# Tesla_MMC.net
KiCad netlist of a schematic drawn in Altium Designer
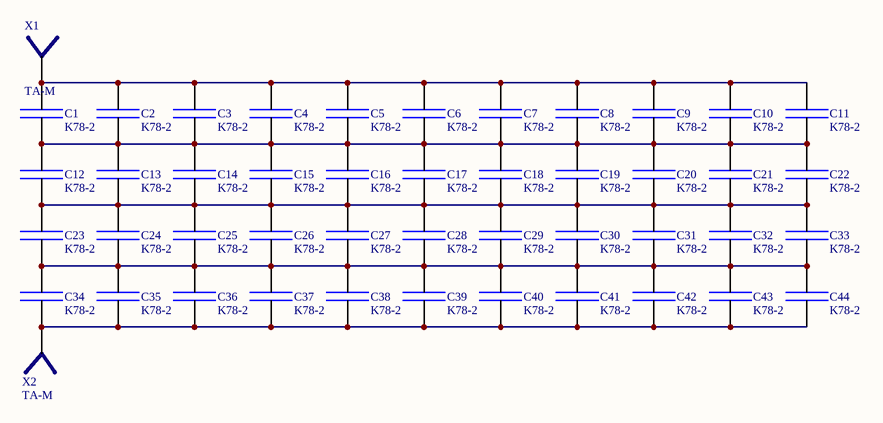
[diagram p0: Tesla_MMC.SchDoc]

(export (version "E")
  (design (tool "Eeschema 10.0.6"))
  (components
    (comp (ref "C1")
      (value "K78-2")
      (footprint "Capasitor K78-2")
      (libsource (lib "NEW") (part "Capasitor_K78-2"))
    )
    (comp (ref "C2")
      (value "K78-2")
      (footprint "Capasitor K78-2")
      (libsource (lib "NEW") (part "Capasitor_K78-2"))
    )
    (comp (ref "C3")
      (value "K78-2")
      (footprint "Capasitor K78-2")
      (libsource (lib "NEW") (part "Capasitor_K78-2"))
    )
    (comp (ref "C4")
      (value "K78-2")
      (footprint "Capasitor K78-2")
      (libsource (lib "NEW") (part "Capasitor_K78-2"))
    )
    (comp (ref "C5")
      (value "K78-2")
      (footprint "Capasitor K78-2")
      (libsource (lib "NEW") (part "Capasitor_K78-2"))
    )
    (comp (ref "C6")
      (value "K78-2")
      (footprint "Capasitor K78-2")
      (libsource (lib "NEW") (part "Capasitor_K78-2"))
    )
    (comp (ref "C7")
      (value "K78-2")
      (footprint "Capasitor K78-2")
      (libsource (lib "NEW") (part "Capasitor_K78-2"))
    )
    (comp (ref "C8")
      (value "K78-2")
      (footprint "Capasitor K78-2")
      (libsource (lib "NEW") (part "Capasitor_K78-2"))
    )
    (comp (ref "C9")
      (value "K78-2")
      (footprint "Capasitor K78-2")
      (libsource (lib "NEW") (part "Capasitor_K78-2"))
    )
    (comp (ref "C10")
      (value "K78-2")
      (footprint "Capasitor K78-2")
      (libsource (lib "NEW") (part "Capasitor_K78-2"))
    )
    (comp (ref "C11")
      (value "K78-2")
      (footprint "Capasitor K78-2")
      (libsource (lib "NEW") (part "Capasitor_K78-2"))
    )
    (comp (ref "C12")
      (value "K78-2")
      (footprint "Capasitor K78-2")
      (libsource (lib "NEW") (part "Capasitor_K78-2"))
    )
    (comp (ref "C13")
      (value "K78-2")
      (footprint "Capasitor K78-2")
      (libsource (lib "NEW") (part "Capasitor_K78-2"))
    )
    (comp (ref "C14")
      (value "K78-2")
      (footprint "Capasitor K78-2")
      (libsource (lib "NEW") (part "Capasitor_K78-2"))
    )
    (comp (ref "C15")
      (value "K78-2")
      (footprint "Capasitor K78-2")
      (libsource (lib "NEW") (part "Capasitor_K78-2"))
    )
    (comp (ref "C16")
      (value "K78-2")
      (footprint "Capasitor K78-2")
      (libsource (lib "NEW") (part "Capasitor_K78-2"))
    )
    (comp (ref "C17")
      (value "K78-2")
      (footprint "Capasitor K78-2")
      (libsource (lib "NEW") (part "Capasitor_K78-2"))
    )
    (comp (ref "C18")
      (value "K78-2")
      (footprint "Capasitor K78-2")
      (libsource (lib "NEW") (part "Capasitor_K78-2"))
    )
    (comp (ref "C19")
      (value "K78-2")
      (footprint "Capasitor K78-2")
      (libsource (lib "NEW") (part "Capasitor_K78-2"))
    )
    (comp (ref "C20")
      (value "K78-2")
      (footprint "Capasitor K78-2")
      (libsource (lib "NEW") (part "Capasitor_K78-2"))
    )
    (comp (ref "C21")
      (value "K78-2")
      (footprint "Capasitor K78-2")
      (libsource (lib "NEW") (part "Capasitor_K78-2"))
    )
    (comp (ref "C22")
      (value "K78-2")
      (footprint "Capasitor K78-2")
      (libsource (lib "NEW") (part "Capasitor_K78-2"))
    )
    (comp (ref "C23")
      (value "K78-2")
      (footprint "Capasitor K78-2")
      (libsource (lib "NEW") (part "Capasitor_K78-2"))
    )
    (comp (ref "C24")
      (value "K78-2")
      (footprint "Capasitor K78-2")
      (libsource (lib "NEW") (part "Capasitor_K78-2"))
    )
    (comp (ref "C25")
      (value "K78-2")
      (footprint "Capasitor K78-2")
      (libsource (lib "NEW") (part "Capasitor_K78-2"))
    )
    (comp (ref "C26")
      (value "K78-2")
      (footprint "Capasitor K78-2")
      (libsource (lib "NEW") (part "Capasitor_K78-2"))
    )
    (comp (ref "C27")
      (value "K78-2")
      (footprint "Capasitor K78-2")
      (libsource (lib "NEW") (part "Capasitor_K78-2"))
    )
    (comp (ref "C28")
      (value "K78-2")
      (footprint "Capasitor K78-2")
      (libsource (lib "NEW") (part "Capasitor_K78-2"))
    )
    (comp (ref "C29")
      (value "K78-2")
      (footprint "Capasitor K78-2")
      (libsource (lib "NEW") (part "Capasitor_K78-2"))
    )
    (comp (ref "C30")
      (value "K78-2")
      (footprint "Capasitor K78-2")
      (libsource (lib "NEW") (part "Capasitor_K78-2"))
    )
    (comp (ref "C31")
      (value "K78-2")
      (footprint "Capasitor K78-2")
      (libsource (lib "NEW") (part "Capasitor_K78-2"))
    )
    (comp (ref "C32")
      (value "K78-2")
      (footprint "Capasitor K78-2")
      (libsource (lib "NEW") (part "Capasitor_K78-2"))
    )
    (comp (ref "C33")
      (value "K78-2")
      (footprint "Capasitor K78-2")
      (libsource (lib "NEW") (part "Capasitor_K78-2"))
    )
    (comp (ref "C34")
      (value "K78-2")
      (footprint "Capasitor K78-2")
      (libsource (lib "NEW") (part "Capasitor_K78-2"))
    )
    (comp (ref "C35")
      (value "K78-2")
      (footprint "Capasitor K78-2")
      (libsource (lib "NEW") (part "Capasitor_K78-2"))
    )
    (comp (ref "C36")
      (value "K78-2")
      (footprint "Capasitor K78-2")
      (libsource (lib "NEW") (part "Capasitor_K78-2"))
    )
    (comp (ref "C37")
      (value "K78-2")
      (footprint "Capasitor K78-2")
      (libsource (lib "NEW") (part "Capasitor_K78-2"))
    )
    (comp (ref "C38")
      (value "K78-2")
      (footprint "Capasitor K78-2")
      (libsource (lib "NEW") (part "Capasitor_K78-2"))
    )
    (comp (ref "C39")
      (value "K78-2")
      (footprint "Capasitor K78-2")
      (libsource (lib "NEW") (part "Capasitor_K78-2"))
    )
    (comp (ref "C40")
      (value "K78-2")
      (footprint "Capasitor K78-2")
      (libsource (lib "NEW") (part "Capasitor_K78-2"))
    )
    (comp (ref "C41")
      (value "K78-2")
      (footprint "Capasitor K78-2")
      (libsource (lib "NEW") (part "Capasitor_K78-2"))
    )
    (comp (ref "C42")
      (value "K78-2")
      (footprint "Capasitor K78-2")
      (libsource (lib "NEW") (part "Capasitor_K78-2"))
    )
    (comp (ref "C43")
      (value "K78-2")
      (footprint "Capasitor K78-2")
      (libsource (lib "NEW") (part "Capasitor_K78-2"))
    )
    (comp (ref "C44")
      (value "K78-2")
      (footprint "Capasitor K78-2")
      (libsource (lib "NEW") (part "Capasitor_K78-2"))
    )
    (comp (ref "X1") (value "TA-M") (footprint "TA-M") (libsource (lib "NEW") (part "TA-M")))
    (comp (ref "X2") (value "TA-M") (footprint "TA-M") (libsource (lib "NEW") (part "TA-M")))
  )
  (nets
    (net (code "1") (name "Net-(C1-Pad1)") (class "Default")
      (node (ref "C1") (pin "1") (pintype "passive"))
      (node (ref "C10") (pin "1") (pintype "passive"))
      (node (ref "C11") (pin "1") (pintype "passive"))
      (node (ref "C2") (pin "1") (pintype "passive"))
      (node (ref "C3") (pin "1") (pintype "passive"))
      (node (ref "C4") (pin "1") (pintype "passive"))
      (node (ref "C5") (pin "1") (pintype "passive"))
      (node (ref "C6") (pin "1") (pintype "passive"))
      (node (ref "C7") (pin "1") (pintype "passive"))
      (node (ref "C8") (pin "1") (pintype "passive"))
      (node (ref "C9") (pin "1") (pintype "passive"))
      (node (ref "X1") (pin "1") (pintype "passive"))
    )
    (net (code "2") (name "Net-(C1-Pad2)") (class "Default")
      (node (ref "C1") (pin "2") (pintype "passive"))
      (node (ref "C10") (pin "2") (pintype "passive"))
      (node (ref "C11") (pin "2") (pintype "passive"))
      (node (ref "C12") (pin "1") (pintype "passive"))
      (node (ref "C13") (pin "1") (pintype "passive"))
      (node (ref "C14") (pin "1") (pintype "passive"))
      (node (ref "C15") (pin "1") (pintype "passive"))
      (node (ref "C16") (pin "1") (pintype "passive"))
      (node (ref "C17") (pin "1") (pintype "passive"))
      (node (ref "C18") (pin "1") (pintype "passive"))
      (node (ref "C19") (pin "1") (pintype "passive"))
      (node (ref "C2") (pin "2") (pintype "passive"))
      (node (ref "C20") (pin "1") (pintype "passive"))
      (node (ref "C21") (pin "1") (pintype "passive"))
      (node (ref "C22") (pin "1") (pintype "passive"))
      (node (ref "C3") (pin "2") (pintype "passive"))
      (node (ref "C4") (pin "2") (pintype "passive"))
      (node (ref "C5") (pin "2") (pintype "passive"))
      (node (ref "C6") (pin "2") (pintype "passive"))
      (node (ref "C7") (pin "2") (pintype "passive"))
      (node (ref "C8") (pin "2") (pintype "passive"))
      (node (ref "C9") (pin "2") (pintype "passive"))
    )
    (net (code "3") (name "Net-(C12-Pad2)") (class "Default")
      (node (ref "C12") (pin "2") (pintype "passive"))
      (node (ref "C13") (pin "2") (pintype "passive"))
      (node (ref "C14") (pin "2") (pintype "passive"))
      (node (ref "C15") (pin "2") (pintype "passive"))
      (node (ref "C16") (pin "2") (pintype "passive"))
      (node (ref "C17") (pin "2") (pintype "passive"))
      (node (ref "C18") (pin "2") (pintype "passive"))
      (node (ref "C19") (pin "2") (pintype "passive"))
      (node (ref "C20") (pin "2") (pintype "passive"))
      (node (ref "C21") (pin "2") (pintype "passive"))
      (node (ref "C22") (pin "2") (pintype "passive"))
      (node (ref "C23") (pin "1") (pintype "passive"))
      (node (ref "C24") (pin "1") (pintype "passive"))
      (node (ref "C25") (pin "1") (pintype "passive"))
      (node (ref "C26") (pin "1") (pintype "passive"))
      (node (ref "C27") (pin "1") (pintype "passive"))
      (node (ref "C28") (pin "1") (pintype "passive"))
      (node (ref "C29") (pin "1") (pintype "passive"))
      (node (ref "C30") (pin "1") (pintype "passive"))
      (node (ref "C31") (pin "1") (pintype "passive"))
      (node (ref "C32") (pin "1") (pintype "passive"))
      (node (ref "C33") (pin "1") (pintype "passive"))
    )
    (net (code "4") (name "Net-(C23-Pad2)") (class "Default")
      (node (ref "C23") (pin "2") (pintype "passive"))
      (node (ref "C24") (pin "2") (pintype "passive"))
      (node (ref "C25") (pin "2") (pintype "passive"))
      (node (ref "C26") (pin "2") (pintype "passive"))
      (node (ref "C27") (pin "2") (pintype "passive"))
      (node (ref "C28") (pin "2") (pintype "passive"))
      (node (ref "C29") (pin "2") (pintype "passive"))
      (node (ref "C30") (pin "2") (pintype "passive"))
      (node (ref "C31") (pin "2") (pintype "passive"))
      (node (ref "C32") (pin "2") (pintype "passive"))
      (node (ref "C33") (pin "2") (pintype "passive"))
      (node (ref "C34") (pin "1") (pintype "passive"))
      (node (ref "C35") (pin "1") (pintype "passive"))
      (node (ref "C36") (pin "1") (pintype "passive"))
      (node (ref "C37") (pin "1") (pintype "passive"))
      (node (ref "C38") (pin "1") (pintype "passive"))
      (node (ref "C39") (pin "1") (pintype "passive"))
      (node (ref "C40") (pin "1") (pintype "passive"))
      (node (ref "C41") (pin "1") (pintype "passive"))
      (node (ref "C42") (pin "1") (pintype "passive"))
      (node (ref "C43") (pin "1") (pintype "passive"))
      (node (ref "C44") (pin "1") (pintype "passive"))
    )
    (net (code "5") (name "Net-(C34-Pad2)") (class "Default")
      (node (ref "C34") (pin "2") (pintype "passive"))
      (node (ref "C35") (pin "2") (pintype "passive"))
      (node (ref "C36") (pin "2") (pintype "passive"))
      (node (ref "C37") (pin "2") (pintype "passive"))
      (node (ref "C38") (pin "2") (pintype "passive"))
      (node (ref "C39") (pin "2") (pintype "passive"))
      (node (ref "C40") (pin "2") (pintype "passive"))
      (node (ref "C41") (pin "2") (pintype "passive"))
      (node (ref "C42") (pin "2") (pintype "passive"))
      (node (ref "C43") (pin "2") (pintype "passive"))
      (node (ref "C44") (pin "2") (pintype "passive"))
      (node (ref "X2") (pin "1") (pintype "passive"))
    )
  )
)
